# Relay.net
KiCad netlist of a schematic drawn in Altium Designer
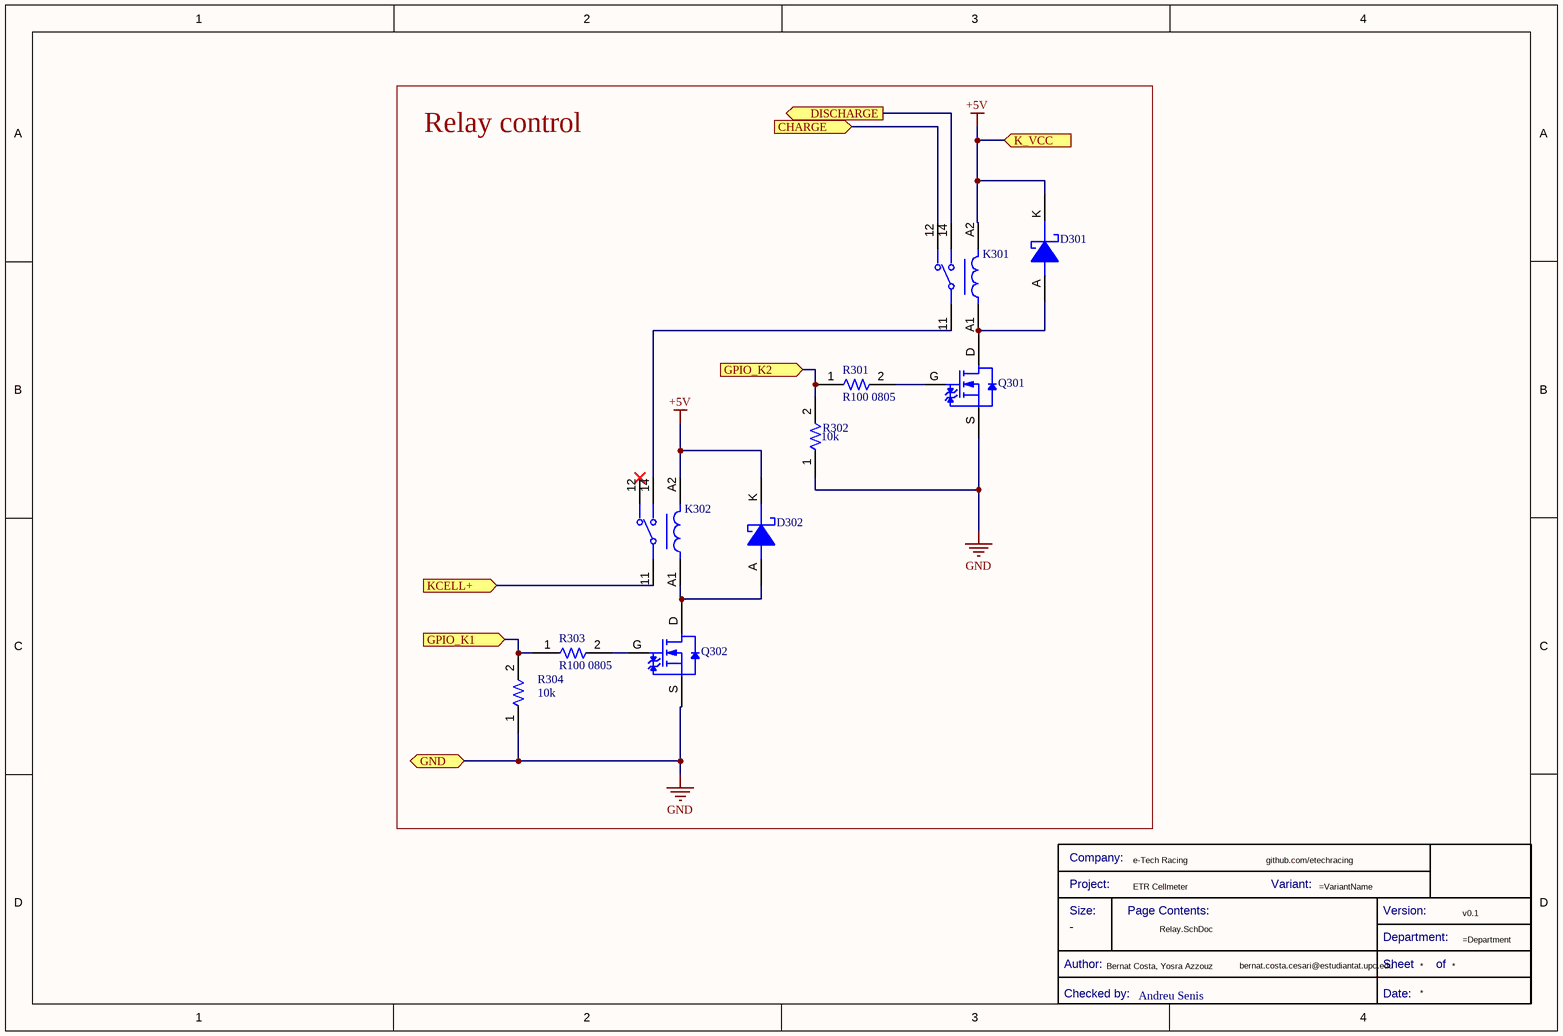
[diagram p0: Relay.SchDoc]

(export (version "E")
  (design (tool "Eeschema 10.0.6"))
  (components
    (comp (ref "*")
      (value "Title Block_template")
      (description "Standard Title Block")
      (fields
        (field (name "SIZE") "-")
        (field (name ".CREATOR") "GP")
        (field (name ".PCBCHECK") "GP")
        (field (name ".SCHCHECK") "GP")
      )
      (libsource (lib "e-Tech_Racing") (part "Title Block_template"))
    )
    (comp (ref "D301")
      (value "DSC-0.5/30-SOD123")
      (footprint "DSC-SOD123")
      (description "VR=30V IF=500mA 30pF P=410mW")
      (fields (field (name ".CREATOR") "GP"))
      (libsource (lib "EMEA- E-Tech Racing- I'Escola d'Enginyeria de Barcelona Est") (part "DSC-0.5/30-SOD123"))
    )
    (comp (ref "D302")
      (value "DSC-0.5/30-SOD123")
      (footprint "DSC-SOD123")
      (description "VR=30V IF=500mA 30pF P=410mW")
      (fields (field (name ".CREATOR") "GP"))
      (libsource (lib "EMEA- E-Tech Racing- I'Escola d'Enginyeria de Barcelona Est") (part "DSC-0.5/30-SOD123"))
    )
    (comp (ref "K301")
      (value "Relay_RZ01-1C4-D005")
      (footprint "FP-1415899-7-MFG")
      (libsource (lib "EMEA- E-Tech Racing- I'Escola d'Enginyeria de Barcelona Est") (part "5e088b4eeede5deee4b60b77e0ea9e2"))
    )
    (comp (ref "K302")
      (value "Relay_RZ01-1C4-D005")
      (footprint "FP-1415899-7-MFG")
      (libsource (lib "EMEA- E-Tech Racing- I'Escola d'Enginyeria de Barcelona Est") (part "5e088b4eeede5deee4b60b77e0ea9e2"))
    )
    (comp (ref "Q301")
      (value "SQ2318CES-T1_GE3")
      (footprint "SOT95P245X110-3N")
      (description "Mosfet, N-channel, 40V, 7A, SOT-23 Rohs Compliant: Yes")
      (libsource (lib "EMEA- E-Tech Racing- I'Escola d'Enginyeria de Barcelona Est") (part "TRT-NCH-3/35-CPH"))
    )
    (comp (ref "Q302")
      (value "SQ2318CES-T1_GE3")
      (footprint "SOT95P245X110-3N")
      (description "Mosfet, N-channel, 40V, 7A, SOT-23 Rohs Compliant: Yes")
      (libsource (lib "EMEA- E-Tech Racing- I'Escola d'Enginyeria de Barcelona Est") (part "TRT-NCH-3/35-CPH"))
    )
    (comp (ref "R301")
      (value "R100 0805")
      (footprint "R0805FTK")
      (description "Res Thick Film 0805 100 Ohm 1% 1/8W ±100ppm/°C Molded SMD SMD Paper Tape on Plastic Reel")
      (fields (field (name "TOLERANCE") "1%") (field (name ".CREATOR") "DR"))
      (libsource (lib "EMEA- E-Tech Racing- I'Escola d'Enginyeria de Barcelona Est") (part "MPT35A1R0F"))
    )
    (comp (ref "R302")
      (value "10k")
      (footprint "R0805FTK")
      (fields
        (field (name "TOLERANCE") "5%")
        (field (name "Comment") "R10k-0805FTK")
        (field (name ".CREATOR") "DR")
      )
      (libsource (lib "EMEA- E-Tech Racing- I'Escola d'Enginyeria de Barcelona Est") (part "R"))
    )
    (comp (ref "R303")
      (value "R100 0805")
      (footprint "R0805FTK")
      (description "Res Thick Film 0805 100 Ohm 1% 1/8W ±100ppm/°C Molded SMD SMD Paper Tape on Plastic Reel")
      (fields (field (name "TOLERANCE") "1%") (field (name ".CREATOR") "DR"))
      (libsource (lib "EMEA- E-Tech Racing- I'Escola d'Enginyeria de Barcelona Est") (part "MPT35A1R0F"))
    )
    (comp (ref "R304")
      (value "10k")
      (footprint "R0805FTK")
      (fields
        (field (name "TOLERANCE") "5%")
        (field (name "Comment") "R10k-0805FTK")
        (field (name ".CREATOR") "DR")
      )
      (libsource (lib "EMEA- E-Tech Racing- I'Escola d'Enginyeria de Barcelona Est") (part "R"))
    )
  )
  (nets
    (net (code "1") (name "+5V") (class "Default")
      (node (ref "D301") (pin "K") (pinfunction "K_K") (pintype "passive"))
      (node (ref "D302") (pin "K") (pinfunction "K_K") (pintype "passive"))
      (node (ref "K301") (pin "A2") (pinfunction "A2_A2") (pintype "passive"))
      (node (ref "K302") (pin "A2") (pinfunction "A2_A2") (pintype "passive"))
    )
    (net (code "2") (name "/CHARGE") (class "Default")
      (node (ref "K301") (pin "12") (pinfunction "12_12") (pintype "passive"))
    )
    (net (code "3") (name "/DISCHARGE") (class "Default")
      (node (ref "K301") (pin "14") (pinfunction "14_14") (pintype "passive"))
    )
    (net (code "4") (name "/GPIO_K1") (class "Default")
      (node (ref "R303") (pin "1") (pinfunction "1_1") (pintype "passive"))
      (node (ref "R304") (pin "2") (pinfunction "2_2") (pintype "passive"))
    )
    (net (code "5") (name "/GPIO_K2") (class "Default")
      (node (ref "R301") (pin "1") (pinfunction "1_1") (pintype "passive"))
      (node (ref "R302") (pin "2") (pinfunction "2_2") (pintype "passive"))
    )
    (net (code "6") (name "/KCELL+") (class "Default")
      (node (ref "K302") (pin "11") (pinfunction "11_11") (pintype "passive"))
    )
    (net (code "7") (name "GND") (class "Default")
      (node (ref "Q301") (pin "S") (pinfunction "S_S") (pintype "passive"))
      (node (ref "Q302") (pin "S") (pinfunction "S_S") (pintype "passive"))
      (node (ref "R302") (pin "1") (pinfunction "1_1") (pintype "passive"))
      (node (ref "R304") (pin "1") (pinfunction "1_1") (pintype "passive"))
    )
    (net (code "8") (name "Net-(D301-PadA)") (class "Default")
      (node (ref "D301") (pin "A") (pinfunction "A_A") (pintype "passive"))
      (node (ref "K301") (pin "A1") (pinfunction "A1_A1") (pintype "passive"))
      (node (ref "Q301") (pin "D") (pinfunction "D_D") (pintype "passive"))
    )
    (net (code "9") (name "Net-(D302-PadA)") (class "Default")
      (node (ref "D302") (pin "A") (pinfunction "A_A") (pintype "passive"))
      (node (ref "K302") (pin "A1") (pinfunction "A1_A1") (pintype "passive"))
      (node (ref "Q302") (pin "D") (pinfunction "D_D") (pintype "passive"))
    )
    (net (code "10") (name "Net-(K301-Pad11)") (class "Default")
      (node (ref "K301") (pin "11") (pinfunction "11_11") (pintype "passive"))
      (node (ref "K302") (pin "14") (pinfunction "14_14") (pintype "passive"))
    )
    (net (code "11") (name "Net-(Q301-PadG)") (class "Default")
      (node (ref "Q301") (pin "G") (pinfunction "G_G") (pintype "passive"))
      (node (ref "R301") (pin "2") (pinfunction "2_2") (pintype "passive"))
    )
    (net (code "12") (name "Net-(Q302-PadG)") (class "Default")
      (node (ref "Q302") (pin "G") (pinfunction "G_G") (pintype "passive"))
      (node (ref "R303") (pin "2") (pinfunction "2_2") (pintype "passive"))
    )
    (net (code "13") (name "unconnected-(K302-Pad12)") (class "Default")
      (node (ref "K302") (pin "12") (pinfunction "12_12") (pintype "passive+no_connect"))
    )
  )
)
